# Hardware_X_Paper.net
KiCad netlist of a schematic drawn in EAGLE
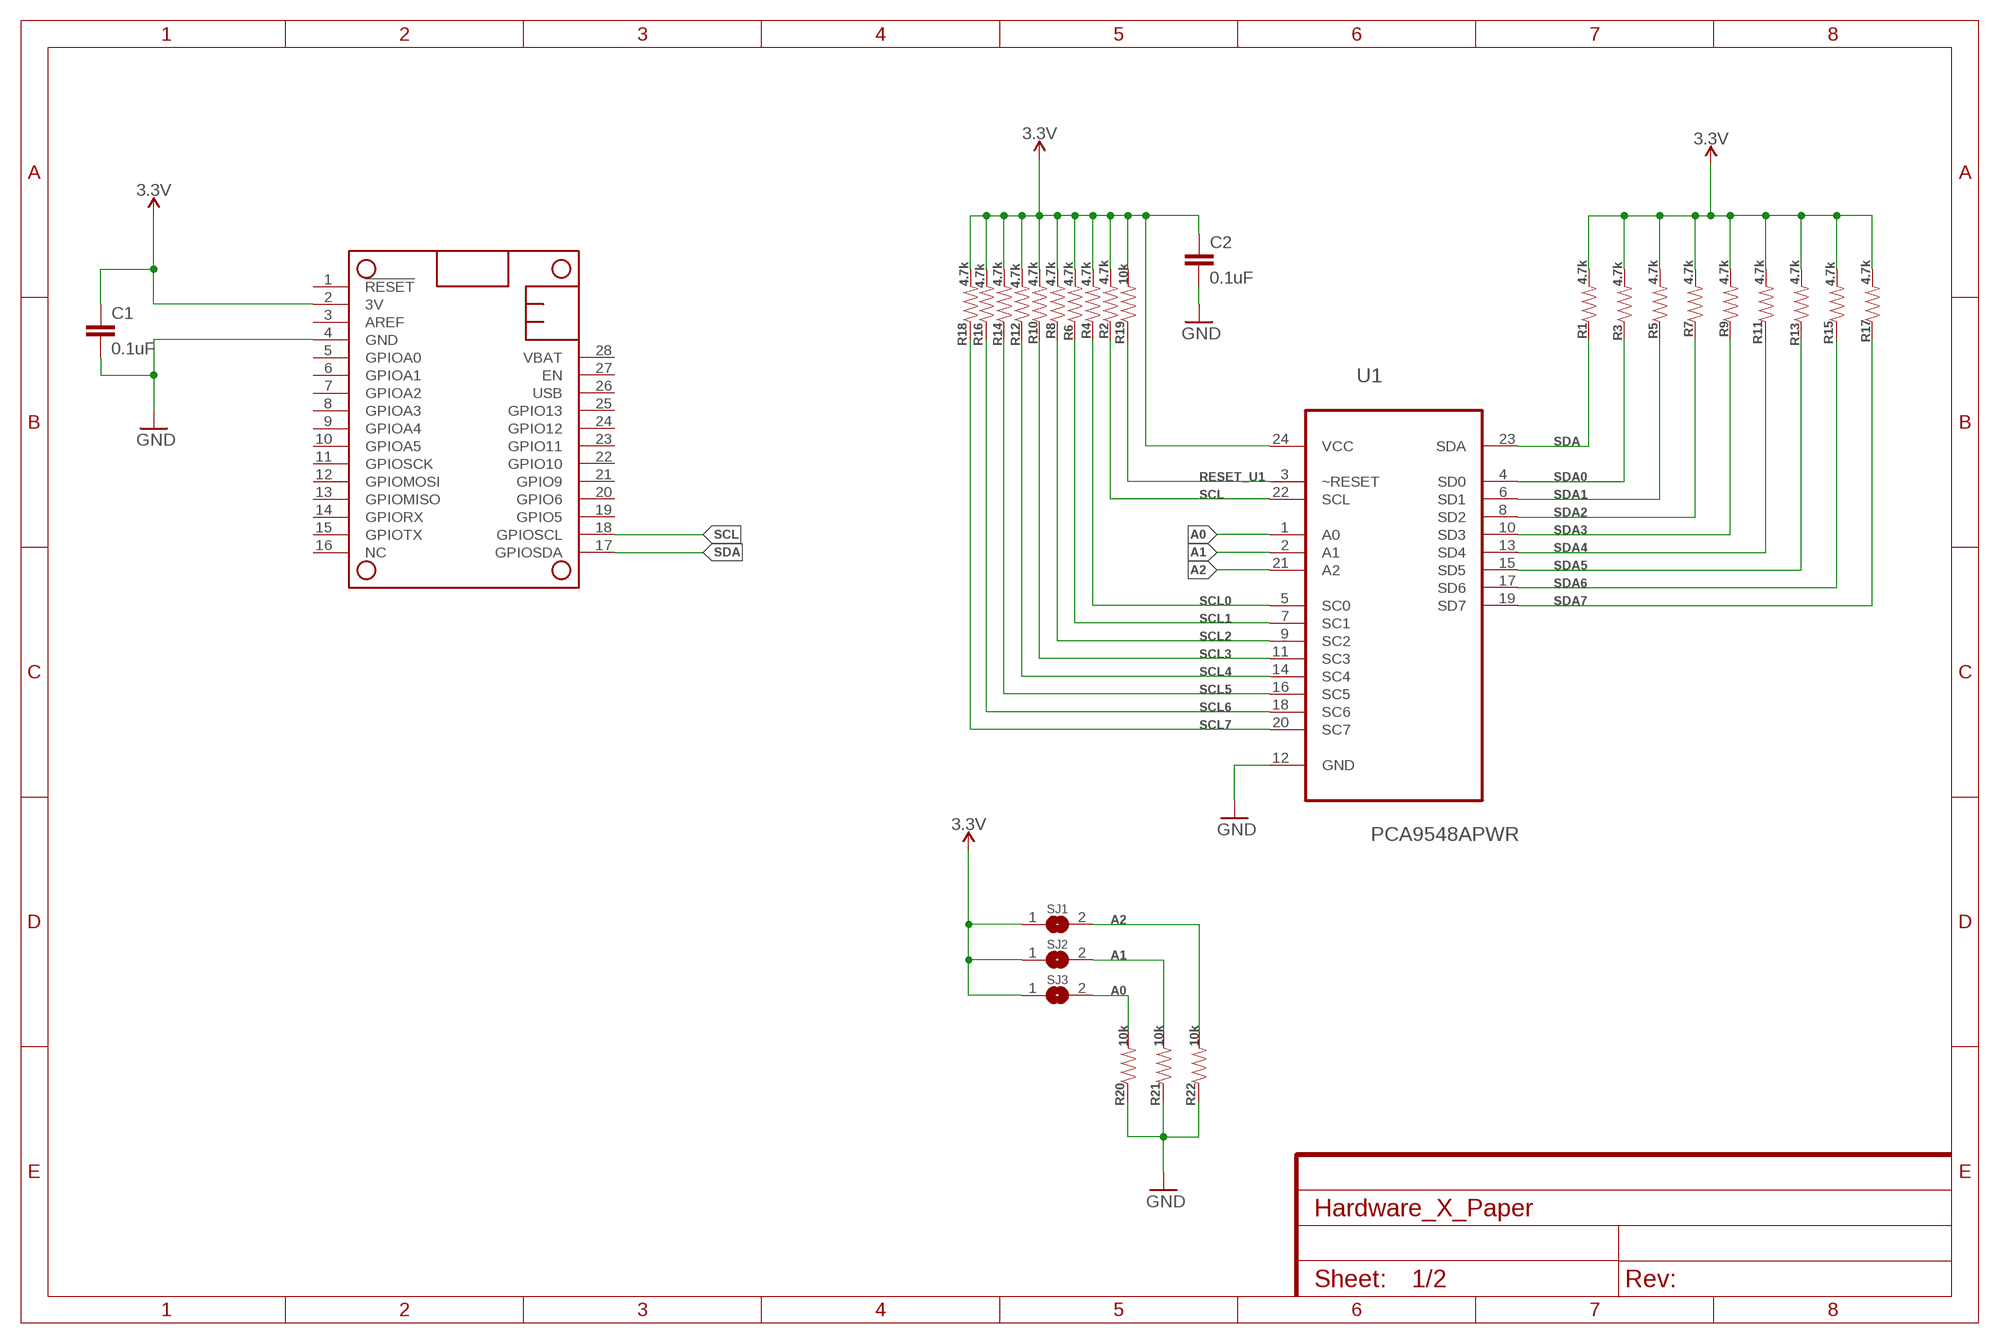
[diagram p0: schematic, sheet 1]
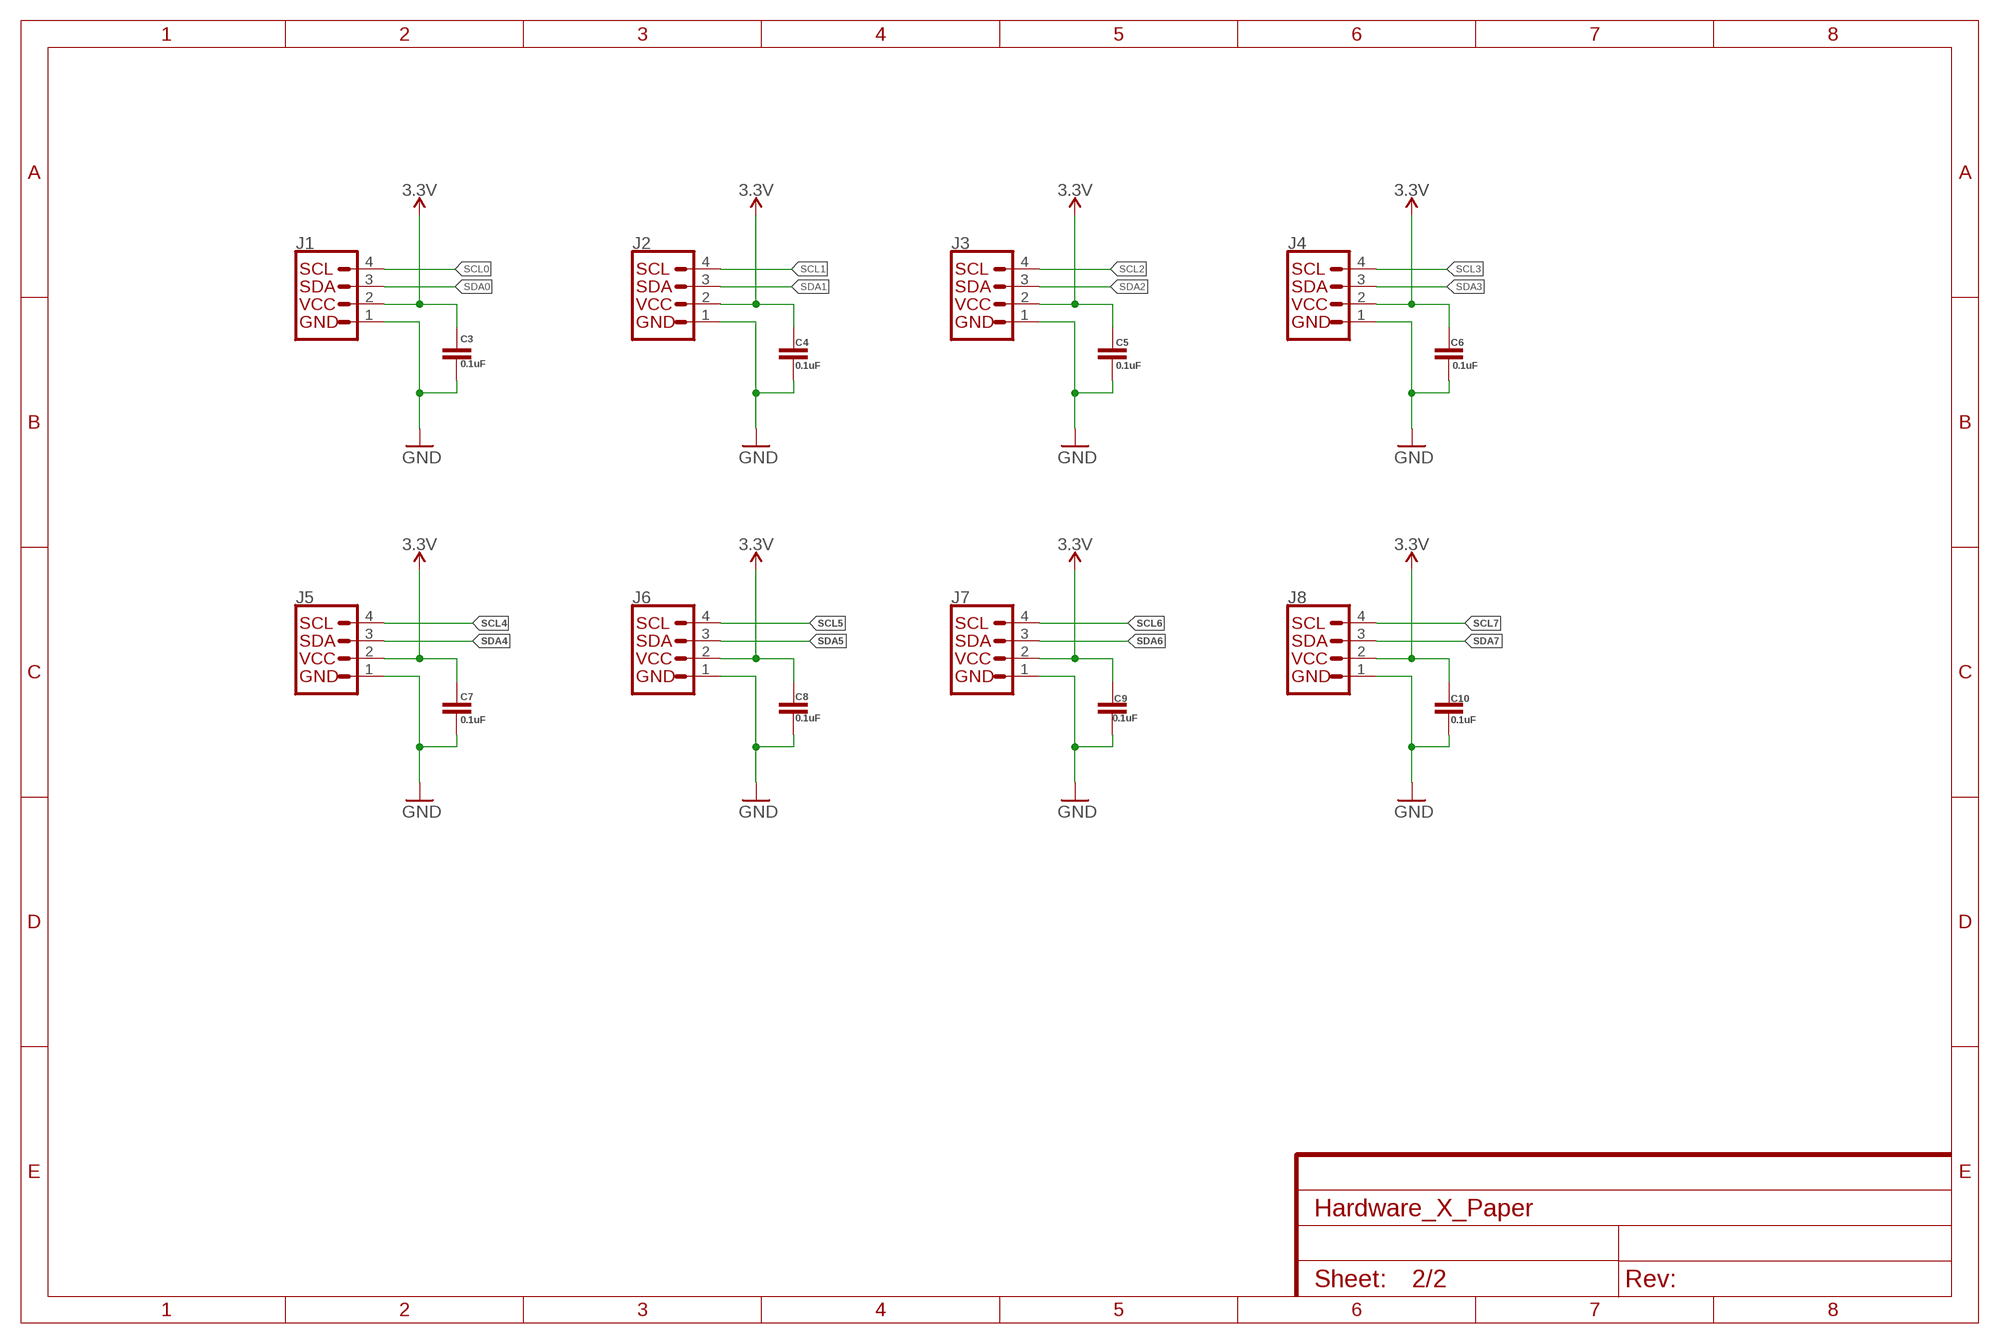
[diagram p1: schematic, sheet 2]

(export (version "E")
  (design (tool "Eeschema 10.0.6"))
  (components
    (comp (ref "C1")
      (value "0.1uF")
      (footprint "eagle-import:0603")
      (libsource (lib "eagle-import") (part "0.1UF-0603-25V-(+80/-20%)"))
    )
    (comp (ref "C2")
      (value "0.1uF")
      (footprint "eagle-import:0603")
      (libsource (lib "eagle-import") (part "0.1UF-0603-25V-(+80/-20%)"))
    )
    (comp (ref "MS1")
      (value "MICROBUILDER_FEATHERWING_NOHOLES")
      (footprint "eagle-import:MICROBUILDER_FEATHERWING_NOHOLES")
      (libsource (lib "eagle-import") (part "MICROBUILDER_FEATHERWING_NOHOLES"))
    )
    (comp (ref "R1")
      (value "4.7k")
      (footprint "eagle-import:0603")
      (libsource (lib "eagle-import") (part "4.7KOHM-0603-1/10W-1%"))
    )
    (comp (ref "R2")
      (value "4.7k")
      (footprint "eagle-import:0603")
      (libsource (lib "eagle-import") (part "4.7KOHM-0603-1/10W-1%"))
    )
    (comp (ref "R3")
      (value "4.7k")
      (footprint "eagle-import:0603")
      (libsource (lib "eagle-import") (part "4.7KOHM-0603-1/10W-1%"))
    )
    (comp (ref "R4")
      (value "4.7k")
      (footprint "eagle-import:0603")
      (libsource (lib "eagle-import") (part "4.7KOHM-0603-1/10W-1%"))
    )
    (comp (ref "R5")
      (value "4.7k")
      (footprint "eagle-import:0603")
      (libsource (lib "eagle-import") (part "4.7KOHM-0603-1/10W-1%"))
    )
    (comp (ref "R6")
      (value "4.7k")
      (footprint "eagle-import:0603")
      (libsource (lib "eagle-import") (part "4.7KOHM-0603-1/10W-1%"))
    )
    (comp (ref "R7")
      (value "4.7k")
      (footprint "eagle-import:0603")
      (libsource (lib "eagle-import") (part "4.7KOHM-0603-1/10W-1%"))
    )
    (comp (ref "R8")
      (value "4.7k")
      (footprint "eagle-import:0603")
      (libsource (lib "eagle-import") (part "4.7KOHM-0603-1/10W-1%"))
    )
    (comp (ref "R9")
      (value "4.7k")
      (footprint "eagle-import:0603")
      (libsource (lib "eagle-import") (part "4.7KOHM-0603-1/10W-1%"))
    )
    (comp (ref "R10")
      (value "4.7k")
      (footprint "eagle-import:0603")
      (libsource (lib "eagle-import") (part "4.7KOHM-0603-1/10W-1%"))
    )
    (comp (ref "R11")
      (value "4.7k")
      (footprint "eagle-import:0603")
      (libsource (lib "eagle-import") (part "4.7KOHM-0603-1/10W-1%"))
    )
    (comp (ref "R12")
      (value "4.7k")
      (footprint "eagle-import:0603")
      (libsource (lib "eagle-import") (part "4.7KOHM-0603-1/10W-1%"))
    )
    (comp (ref "R13")
      (value "4.7k")
      (footprint "eagle-import:0603")
      (libsource (lib "eagle-import") (part "4.7KOHM-0603-1/10W-1%"))
    )
    (comp (ref "R14")
      (value "4.7k")
      (footprint "eagle-import:0603")
      (libsource (lib "eagle-import") (part "4.7KOHM-0603-1/10W-1%"))
    )
    (comp (ref "R15")
      (value "4.7k")
      (footprint "eagle-import:0603")
      (libsource (lib "eagle-import") (part "4.7KOHM-0603-1/10W-1%"))
    )
    (comp (ref "R16")
      (value "4.7k")
      (footprint "eagle-import:0603")
      (libsource (lib "eagle-import") (part "4.7KOHM-0603-1/10W-1%"))
    )
    (comp (ref "R17")
      (value "4.7k")
      (footprint "eagle-import:0603")
      (libsource (lib "eagle-import") (part "4.7KOHM-0603-1/10W-1%"))
    )
    (comp (ref "R18")
      (value "4.7k")
      (footprint "eagle-import:0603")
      (libsource (lib "eagle-import") (part "4.7KOHM-0603-1/10W-1%"))
    )
    (comp (ref "R19")
      (value "10k")
      (footprint "eagle-import:0603")
      (libsource (lib "eagle-import") (part "10KOHM-0603-1/10W-1%"))
    )
    (comp (ref "R20")
      (value "10k")
      (footprint "eagle-import:0603")
      (libsource (lib "eagle-import") (part "10KOHM-0603-1/10W-1%"))
    )
    (comp (ref "R21")
      (value "10k")
      (footprint "eagle-import:0603")
      (libsource (lib "eagle-import") (part "10KOHM-0603-1/10W-1%"))
    )
    (comp (ref "R22")
      (value "10k")
      (footprint "eagle-import:0603")
      (libsource (lib "eagle-import") (part "10KOHM-0603-1/10W-1%"))
    )
    (comp (ref "SJ1")
      (value "MICROBUILDER_SOLDERJUMPER")
      (footprint "eagle-import:MICROBUILDER_SOLDERJUMPER_ARROW_NOPASTE")
      (libsource (lib "eagle-import") (part "MICROBUILDER_SOLDERJUMPER"))
    )
    (comp (ref "SJ2")
      (value "MICROBUILDER_SOLDERJUMPER")
      (footprint "eagle-import:MICROBUILDER_SOLDERJUMPER_ARROW_NOPASTE")
      (libsource (lib "eagle-import") (part "MICROBUILDER_SOLDERJUMPER"))
    )
    (comp (ref "SJ3")
      (value "MICROBUILDER_SOLDERJUMPER")
      (footprint "eagle-import:MICROBUILDER_SOLDERJUMPER_ARROW_NOPASTE")
      (libsource (lib "eagle-import") (part "MICROBUILDER_SOLDERJUMPER"))
    )
    (comp (ref "U1")
      (value "PCA9548APWR")
      (footprint "eagle-import:SOP65P640X120-24N")
      (fields (field (name "MF") "Texas Instruments"))
      (libsource (lib "eagle-import") (part "PCA9548APWR"))
    )
    (comp (ref "C3")
      (value "0.1uF")
      (footprint "eagle-import:0603")
      (libsource (lib "eagle-import") (part "0.1UF-0603-25V-(+80/-20%)"))
    )
    (comp (ref "C4")
      (value "0.1uF")
      (footprint "eagle-import:0603")
      (libsource (lib "eagle-import") (part "0.1UF-0603-25V-(+80/-20%)"))
    )
    (comp (ref "C5")
      (value "0.1uF")
      (footprint "eagle-import:0603")
      (libsource (lib "eagle-import") (part "0.1UF-0603-25V-(+80/-20%)"))
    )
    (comp (ref "C6")
      (value "0.1uF")
      (footprint "eagle-import:0603")
      (libsource (lib "eagle-import") (part "0.1UF-0603-25V-(+80/-20%)"))
    )
    (comp (ref "C7")
      (value "0.1uF")
      (footprint "eagle-import:0603")
      (libsource (lib "eagle-import") (part "0.1UF-0603-25V-(+80/-20%)"))
    )
    (comp (ref "C8")
      (value "0.1uF")
      (footprint "eagle-import:0603")
      (libsource (lib "eagle-import") (part "0.1UF-0603-25V-(+80/-20%)"))
    )
    (comp (ref "C9")
      (value "0.1uF")
      (footprint "eagle-import:0603")
      (libsource (lib "eagle-import") (part "0.1UF-0603-25V-(+80/-20%)"))
    )
    (comp (ref "C10")
      (value "0.1uF")
      (footprint "eagle-import:0603")
      (libsource (lib "eagle-import") (part "0.1UF-0603-25V-(+80/-20%)"))
    )
    (comp (ref "J1")
      (value "QWIIC_CONNECTORJS-1MM")
      (footprint "eagle-import:1X04_1MM_RA")
      (libsource (lib "eagle-import") (part "QWIIC_CONNECTORJS-1MM"))
    )
    (comp (ref "J2")
      (value "QWIIC_CONNECTORJS-1MM")
      (footprint "eagle-import:1X04_1MM_RA")
      (libsource (lib "eagle-import") (part "QWIIC_CONNECTORJS-1MM"))
    )
    (comp (ref "J3")
      (value "QWIIC_CONNECTORJS-1MM")
      (footprint "eagle-import:1X04_1MM_RA")
      (libsource (lib "eagle-import") (part "QWIIC_CONNECTORJS-1MM"))
    )
    (comp (ref "J4")
      (value "QWIIC_CONNECTORJS-1MM")
      (footprint "eagle-import:1X04_1MM_RA")
      (libsource (lib "eagle-import") (part "QWIIC_CONNECTORJS-1MM"))
    )
    (comp (ref "J5")
      (value "QWIIC_CONNECTORJS-1MM")
      (footprint "eagle-import:1X04_1MM_RA")
      (libsource (lib "eagle-import") (part "QWIIC_CONNECTORJS-1MM"))
    )
    (comp (ref "J6")
      (value "QWIIC_CONNECTORJS-1MM")
      (footprint "eagle-import:1X04_1MM_RA")
      (libsource (lib "eagle-import") (part "QWIIC_CONNECTORJS-1MM"))
    )
    (comp (ref "J7")
      (value "QWIIC_CONNECTORJS-1MM")
      (footprint "eagle-import:1X04_1MM_RA")
      (libsource (lib "eagle-import") (part "QWIIC_CONNECTORJS-1MM"))
    )
    (comp (ref "J8")
      (value "QWIIC_CONNECTORJS-1MM")
      (footprint "eagle-import:1X04_1MM_RA")
      (libsource (lib "eagle-import") (part "QWIIC_CONNECTORJS-1MM"))
    )
  )
  (nets
    (net (code "1") (name "3.3V") (class "Default")
      (node (ref "C1") (pin "1") (pinfunction "1_1") (pintype "passive"))
      (node (ref "C10") (pin "1") (pinfunction "1_1") (pintype "passive"))
      (node (ref "C2") (pin "1") (pinfunction "1_1") (pintype "passive"))
      (node (ref "C3") (pin "1") (pinfunction "1_1") (pintype "passive"))
      (node (ref "C4") (pin "1") (pinfunction "1_1") (pintype "passive"))
      (node (ref "C5") (pin "1") (pinfunction "1_1") (pintype "passive"))
      (node (ref "C6") (pin "1") (pinfunction "1_1") (pintype "passive"))
      (node (ref "C7") (pin "1") (pinfunction "1_1") (pintype "passive"))
      (node (ref "C8") (pin "1") (pinfunction "1_1") (pintype "passive"))
      (node (ref "C9") (pin "1") (pinfunction "1_1") (pintype "passive"))
      (node (ref "J1") (pin "2") (pinfunction "VCC_2") (pintype "power_in"))
      (node (ref "J2") (pin "2") (pinfunction "VCC_2") (pintype "power_in"))
      (node (ref "J3") (pin "2") (pinfunction "VCC_2") (pintype "power_in"))
      (node (ref "J4") (pin "2") (pinfunction "VCC_2") (pintype "power_in"))
      (node (ref "J5") (pin "2") (pinfunction "VCC_2") (pintype "power_in"))
      (node (ref "J6") (pin "2") (pinfunction "VCC_2") (pintype "power_in"))
      (node (ref "J7") (pin "2") (pinfunction "VCC_2") (pintype "power_in"))
      (node (ref "J8") (pin "2") (pinfunction "VCC_2") (pintype "power_in"))
      (node (ref "MS1") (pin "2") (pinfunction "3V_2") (pintype "power_in"))
      (node (ref "R1") (pin "2") (pinfunction "2_2") (pintype "passive"))
      (node (ref "R10") (pin "2") (pinfunction "2_2") (pintype "passive"))
      (node (ref "R11") (pin "2") (pinfunction "2_2") (pintype "passive"))
      (node (ref "R12") (pin "2") (pinfunction "2_2") (pintype "passive"))
      (node (ref "R13") (pin "2") (pinfunction "2_2") (pintype "passive"))
      (node (ref "R14") (pin "2") (pinfunction "2_2") (pintype "passive"))
      (node (ref "R15") (pin "2") (pinfunction "2_2") (pintype "passive"))
      (node (ref "R16") (pin "2") (pinfunction "2_2") (pintype "passive"))
      (node (ref "R17") (pin "2") (pinfunction "2_2") (pintype "passive"))
      (node (ref "R18") (pin "2") (pinfunction "2_2") (pintype "passive"))
      (node (ref "R19") (pin "2") (pinfunction "2_2") (pintype "passive"))
      (node (ref "R2") (pin "2") (pinfunction "2_2") (pintype "passive"))
      (node (ref "R3") (pin "2") (pinfunction "2_2") (pintype "passive"))
      (node (ref "R4") (pin "2") (pinfunction "2_2") (pintype "passive"))
      (node (ref "R5") (pin "2") (pinfunction "2_2") (pintype "passive"))
      (node (ref "R6") (pin "2") (pinfunction "2_2") (pintype "passive"))
      (node (ref "R7") (pin "2") (pinfunction "2_2") (pintype "passive"))
      (node (ref "R8") (pin "2") (pinfunction "2_2") (pintype "passive"))
      (node (ref "R9") (pin "2") (pinfunction "2_2") (pintype "passive"))
      (node (ref "SJ1") (pin "1") (pinfunction "1_1") (pintype "passive"))
      (node (ref "SJ2") (pin "1") (pinfunction "1_1") (pintype "passive"))
      (node (ref "SJ3") (pin "1") (pinfunction "1_1") (pintype "passive"))
      (node (ref "U1") (pin "24") (pinfunction "VCC_24") (pintype "power_in"))
    )
    (net (code "2") (name "A0") (class "Default")
      (node (ref "R20") (pin "2") (pinfunction "2_2") (pintype "passive"))
      (node (ref "SJ3") (pin "2") (pinfunction "2_2") (pintype "passive"))
      (node (ref "U1") (pin "1") (pinfunction "A0_1") (pintype "input"))
    )
    (net (code "3") (name "A1") (class "Default")
      (node (ref "R21") (pin "2") (pinfunction "2_2") (pintype "passive"))
      (node (ref "SJ2") (pin "2") (pinfunction "2_2") (pintype "passive"))
      (node (ref "U1") (pin "2") (pinfunction "A1_2") (pintype "input"))
    )
    (net (code "4") (name "A2") (class "Default")
      (node (ref "R22") (pin "2") (pinfunction "2_2") (pintype "passive"))
      (node (ref "SJ1") (pin "2") (pinfunction "2_2") (pintype "passive"))
      (node (ref "U1") (pin "21") (pinfunction "A2_21") (pintype "input"))
    )
    (net (code "5") (name "GND") (class "Default")
      (node (ref "C1") (pin "2") (pinfunction "2_2") (pintype "passive"))
      (node (ref "C10") (pin "2") (pinfunction "2_2") (pintype "passive"))
      (node (ref "C2") (pin "2") (pinfunction "2_2") (pintype "passive"))
      (node (ref "C3") (pin "2") (pinfunction "2_2") (pintype "passive"))
      (node (ref "C4") (pin "2") (pinfunction "2_2") (pintype "passive"))
      (node (ref "C5") (pin "2") (pinfunction "2_2") (pintype "passive"))
      (node (ref "C6") (pin "2") (pinfunction "2_2") (pintype "passive"))
      (node (ref "C7") (pin "2") (pinfunction "2_2") (pintype "passive"))
      (node (ref "C8") (pin "2") (pinfunction "2_2") (pintype "passive"))
      (node (ref "C9") (pin "2") (pinfunction "2_2") (pintype "passive"))
      (node (ref "J1") (pin "1") (pinfunction "GND_1") (pintype "power_in"))
      (node (ref "J2") (pin "1") (pinfunction "GND_1") (pintype "power_in"))
      (node (ref "J3") (pin "1") (pinfunction "GND_1") (pintype "power_in"))
      (node (ref "J4") (pin "1") (pinfunction "GND_1") (pintype "power_in"))
      (node (ref "J5") (pin "1") (pinfunction "GND_1") (pintype "power_in"))
      (node (ref "J6") (pin "1") (pinfunction "GND_1") (pintype "power_in"))
      (node (ref "J7") (pin "1") (pinfunction "GND_1") (pintype "power_in"))
      (node (ref "J8") (pin "1") (pinfunction "GND_1") (pintype "power_in"))
      (node (ref "MS1") (pin "4") (pinfunction "GND_4") (pintype "power_in"))
      (node (ref "R20") (pin "1") (pinfunction "1_1") (pintype "passive"))
      (node (ref "R21") (pin "1") (pinfunction "1_1") (pintype "passive"))
      (node (ref "R22") (pin "1") (pinfunction "1_1") (pintype "passive"))
      (node (ref "U1") (pin "12") (pinfunction "GND_12") (pintype "passive"))
    )
    (net (code "6") (name "RESET_U1") (class "Default")
      (node (ref "R19") (pin "1") (pinfunction "1_1") (pintype "passive"))
      (node (ref "U1") (pin "3") (pinfunction "~{RESET}_3") (pintype "input"))
    )
    (net (code "7") (name "SCL") (class "Default")
      (node (ref "MS1") (pin "18") (pinfunction "GPIOSCL_18") (pintype "bidirectional"))
      (node (ref "R2") (pin "1") (pinfunction "1_1") (pintype "passive"))
      (node (ref "U1") (pin "22") (pinfunction "SCL_22") (pintype "input"))
    )
    (net (code "8") (name "SCL0") (class "Default")
      (node (ref "J1") (pin "4") (pinfunction "SCL_4") (pintype "passive"))
      (node (ref "R4") (pin "1") (pinfunction "1_1") (pintype "passive"))
      (node (ref "U1") (pin "5") (pinfunction "SC0_5") (pintype "bidirectional"))
    )
    (net (code "9") (name "SCL1") (class "Default")
      (node (ref "J2") (pin "4") (pinfunction "SCL_4") (pintype "passive"))
      (node (ref "R6") (pin "1") (pinfunction "1_1") (pintype "passive"))
      (node (ref "U1") (pin "7") (pinfunction "SC1_7") (pintype "bidirectional"))
    )
    (net (code "10") (name "SCL2") (class "Default")
      (node (ref "J3") (pin "4") (pinfunction "SCL_4") (pintype "passive"))
      (node (ref "R8") (pin "1") (pinfunction "1_1") (pintype "passive"))
      (node (ref "U1") (pin "9") (pinfunction "SC2_9") (pintype "bidirectional"))
    )
    (net (code "11") (name "SCL3") (class "Default")
      (node (ref "J4") (pin "4") (pinfunction "SCL_4") (pintype "passive"))
      (node (ref "R10") (pin "1") (pinfunction "1_1") (pintype "passive"))
      (node (ref "U1") (pin "11") (pinfunction "SC3_11") (pintype "bidirectional"))
    )
    (net (code "12") (name "SCL4") (class "Default")
      (node (ref "J5") (pin "4") (pinfunction "SCL_4") (pintype "passive"))
      (node (ref "R12") (pin "1") (pinfunction "1_1") (pintype "passive"))
      (node (ref "U1") (pin "14") (pinfunction "SC4_14") (pintype "bidirectional"))
    )
    (net (code "13") (name "SCL5") (class "Default")
      (node (ref "J6") (pin "4") (pinfunction "SCL_4") (pintype "passive"))
      (node (ref "R14") (pin "1") (pinfunction "1_1") (pintype "passive"))
      (node (ref "U1") (pin "16") (pinfunction "SC5_16") (pintype "bidirectional"))
    )
    (net (code "14") (name "SCL6") (class "Default")
      (node (ref "J7") (pin "4") (pinfunction "SCL_4") (pintype "passive"))
      (node (ref "R16") (pin "1") (pinfunction "1_1") (pintype "passive"))
      (node (ref "U1") (pin "18") (pinfunction "SC6_18") (pintype "bidirectional"))
    )
    (net (code "15") (name "SCL7") (class "Default")
      (node (ref "J8") (pin "4") (pinfunction "SCL_4") (pintype "passive"))
      (node (ref "R18") (pin "1") (pinfunction "1_1") (pintype "passive"))
      (node (ref "U1") (pin "20") (pinfunction "SC7_20") (pintype "bidirectional"))
    )
    (net (code "16") (name "SDA") (class "Default")
      (node (ref "MS1") (pin "17") (pinfunction "GPIOSDA_17") (pintype "bidirectional"))
      (node (ref "R1") (pin "1") (pinfunction "1_1") (pintype "passive"))
      (node (ref "U1") (pin "23") (pinfunction "SDA_23") (pintype "bidirectional"))
    )
    (net (code "17") (name "SDA0") (class "Default")
      (node (ref "J1") (pin "3") (pinfunction "SDA_3") (pintype "passive"))
      (node (ref "R3") (pin "1") (pinfunction "1_1") (pintype "passive"))
      (node (ref "U1") (pin "4") (pinfunction "SD0_4") (pintype "bidirectional"))
    )
    (net (code "18") (name "SDA1") (class "Default")
      (node (ref "J2") (pin "3") (pinfunction "SDA_3") (pintype "passive"))
      (node (ref "R5") (pin "1") (pinfunction "1_1") (pintype "passive"))
      (node (ref "U1") (pin "6") (pinfunction "SD1_6") (pintype "bidirectional"))
    )
    (net (code "19") (name "SDA2") (class "Default")
      (node (ref "J3") (pin "3") (pinfunction "SDA_3") (pintype "passive"))
      (node (ref "R7") (pin "1") (pinfunction "1_1") (pintype "passive"))
      (node (ref "U1") (pin "8") (pinfunction "SD2_8") (pintype "bidirectional"))
    )
    (net (code "20") (name "SDA3") (class "Default")
      (node (ref "J4") (pin "3") (pinfunction "SDA_3") (pintype "passive"))
      (node (ref "R9") (pin "1") (pinfunction "1_1") (pintype "passive"))
      (node (ref "U1") (pin "10") (pinfunction "SD3_10") (pintype "bidirectional"))
    )
    (net (code "21") (name "SDA4") (class "Default")
      (node (ref "J5") (pin "3") (pinfunction "SDA_3") (pintype "passive"))
      (node (ref "R11") (pin "1") (pinfunction "1_1") (pintype "passive"))
      (node (ref "U1") (pin "13") (pinfunction "SD4_13") (pintype "bidirectional"))
    )
    (net (code "22") (name "SDA5") (class "Default")
      (node (ref "J6") (pin "3") (pinfunction "SDA_3") (pintype "passive"))
      (node (ref "R13") (pin "1") (pinfunction "1_1") (pintype "passive"))
      (node (ref "U1") (pin "15") (pinfunction "SD5_15") (pintype "bidirectional"))
    )
    (net (code "23") (name "SDA6") (class "Default")
      (node (ref "J7") (pin "3") (pinfunction "SDA_3") (pintype "passive"))
      (node (ref "R15") (pin "1") (pinfunction "1_1") (pintype "passive"))
      (node (ref "U1") (pin "17") (pinfunction "SD6_17") (pintype "bidirectional"))
    )
    (net (code "24") (name "SDA7") (class "Default")
      (node (ref "J8") (pin "3") (pinfunction "SDA_3") (pintype "passive"))
      (node (ref "R17") (pin "1") (pinfunction "1_1") (pintype "passive"))
      (node (ref "U1") (pin "19") (pinfunction "SD7_19") (pintype "bidirectional"))
    )
    (net (code "25") (name "USB") (class "Default")
      (node (ref "MS1") (pin "26") (pinfunction "USB_26") (pintype "power_in"))
    )
    (net (code "26") (name "VBAT") (class "Default")
      (node (ref "MS1") (pin "28") (pinfunction "VBAT_28") (pintype "power_in"))
    )
    (net (code "27") (name "unconnected-(MS1-AREF-Pad3)") (class "Default")
      (node (ref "MS1") (pin "3") (pinfunction "AREF_3") (pintype "passive"))
    )
    (net (code "28") (name "unconnected-(MS1-EN-Pad27)") (class "Default")
      (node (ref "MS1") (pin "27") (pinfunction "EN_27") (pintype "passive"))
    )
    (net (code "29") (name "unconnected-(MS1-GPIO5-Pad19)") (class "Default")
      (node (ref "MS1") (pin "19") (pinfunction "GPIO5_19") (pintype "bidirectional"))
    )
    (net (code "30") (name "unconnected-(MS1-GPIO6-Pad20)") (class "Default")
      (node (ref "MS1") (pin "20") (pinfunction "GPIO6_20") (pintype "bidirectional"))
    )
    (net (code "31") (name "unconnected-(MS1-GPIO9-Pad21)") (class "Default")
      (node (ref "MS1") (pin "21") (pinfunction "GPIO9_21") (pintype "bidirectional"))
    )
    (net (code "32") (name "unconnected-(MS1-GPIO10-Pad22)") (class "Default")
      (node (ref "MS1") (pin "22") (pinfunction "GPIO10_22") (pintype "bidirectional"))
    )
    (net (code "33") (name "unconnected-(MS1-GPIO11-Pad23)") (class "Default")
      (node (ref "MS1") (pin "23") (pinfunction "GPIO11_23") (pintype "bidirectional"))
    )
    (net (code "34") (name "unconnected-(MS1-GPIO12-Pad24)") (class "Default")
      (node (ref "MS1") (pin "24") (pinfunction "GPIO12_24") (pintype "bidirectional"))
    )
    (net (code "35") (name "unconnected-(MS1-GPIO13-Pad25)") (class "Default")
      (node (ref "MS1") (pin "25") (pinfunction "GPIO13_25") (pintype "bidirectional"))
    )
    (net (code "36") (name "unconnected-(MS1-GPIOA0-Pad5)") (class "Default")
      (node (ref "MS1") (pin "5") (pinfunction "GPIOA0_5") (pintype "bidirectional"))
    )
    (net (code "37") (name "unconnected-(MS1-GPIOA1-Pad6)") (class "Default")
      (node (ref "MS1") (pin "6") (pinfunction "GPIOA1_6") (pintype "bidirectional"))
    )
    (net (code "38") (name "unconnected-(MS1-GPIOA2-Pad7)") (class "Default")
      (node (ref "MS1") (pin "7") (pinfunction "GPIOA2_7") (pintype "bidirectional"))
    )
    (net (code "39") (name "unconnected-(MS1-GPIOA3-Pad8)") (class "Default")
      (node (ref "MS1") (pin "8") (pinfunction "GPIOA3_8") (pintype "bidirectional"))
    )
    (net (code "40") (name "unconnected-(MS1-GPIOA4-Pad9)") (class "Default")
      (node (ref "MS1") (pin "9") (pinfunction "GPIOA4_9") (pintype "bidirectional"))
    )
    (net (code "41") (name "unconnected-(MS1-GPIOA5-Pad10)") (class "Default")
      (node (ref "MS1") (pin "10") (pinfunction "GPIOA5_10") (pintype "bidirectional"))
    )
    (net (code "42") (name "unconnected-(MS1-GPIOMISO-Pad13)") (class "Default")
      (node (ref "MS1") (pin "13") (pinfunction "GPIOMISO_13") (pintype "bidirectional"))
    )
    (net (code "43") (name "unconnected-(MS1-GPIOMOSI-Pad12)") (class "Default")
      (node (ref "MS1") (pin "12") (pinfunction "GPIOMOSI_12") (pintype "bidirectional"))
    )
    (net (code "44") (name "unconnected-(MS1-GPIORX-Pad14)") (class "Default")
      (node (ref "MS1") (pin "14") (pinfunction "GPIORX_14") (pintype "bidirectional"))
    )
    (net (code "45") (name "unconnected-(MS1-GPIOSCK-Pad11)") (class "Default")
      (node (ref "MS1") (pin "11") (pinfunction "GPIOSCK_11") (pintype "bidirectional"))
    )
    (net (code "46") (name "unconnected-(MS1-GPIOTX-Pad15)") (class "Default")
      (node (ref "MS1") (pin "15") (pinfunction "GPIOTX_15") (pintype "bidirectional"))
    )
    (net (code "47") (name "unconnected-(MS1-NC-Pad16)") (class "Default")
      (node (ref "MS1") (pin "16") (pinfunction "NC_16") (pintype "passive"))
    )
    (net (code "48") (name "unconnected-(MS1-~{RESET}-Pad1)") (class "Default")
      (node (ref "MS1") (pin "1") (pinfunction "~{RESET}_1") (pintype "input"))
    )
  )
)
